# TTK8.net
KiCad netlist of a schematic drawn in Altium Designer
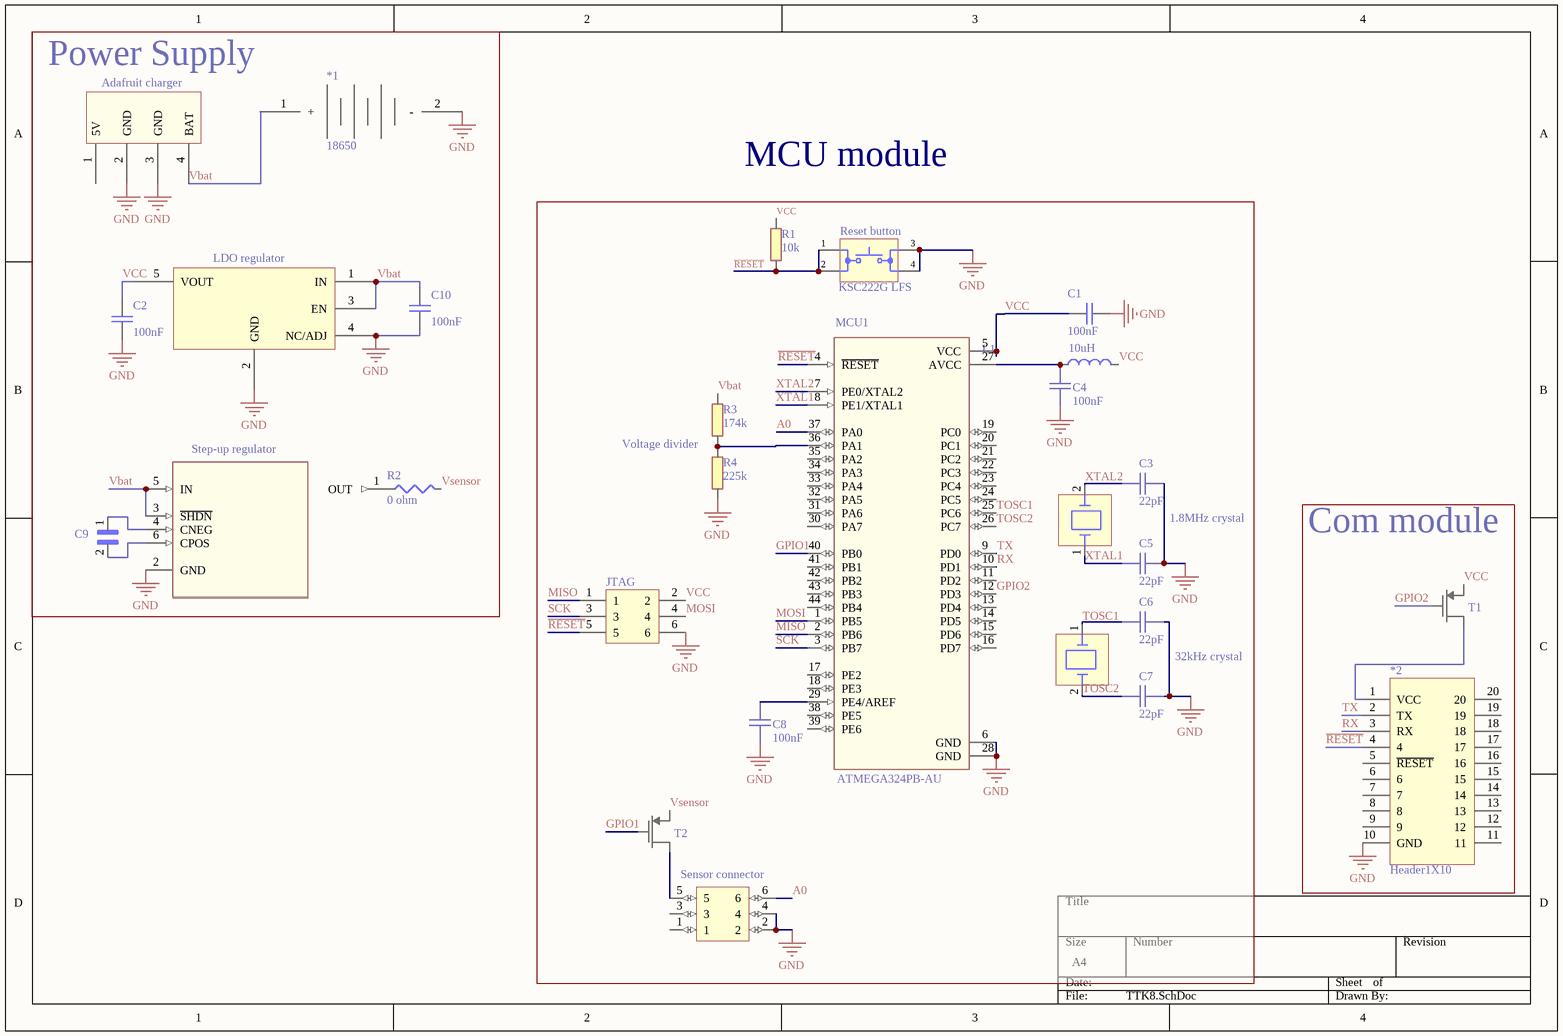
[diagram p0: TTK8.SchDoc]

(export (version "E")
  (design (tool "Eeschema 10.0.6"))
  (components
    (comp (ref "*1") (value "18650") (footprint "18650") (libsource (lib "BatteryHolder") (part "18650")))
    (comp (ref "*2")
      (value "Header1X10")
      (footprint "Header1X10")
      (libsource (lib "Header") (part "Header1X10"))
    )
    (comp (ref "C1")
      (value "100nF")
      (footprint "C0603")
      (description "C0603")
      (fields (field (name "Comment") "02016D104KAT2A"))
      (libsource (lib "Passive components") (part "02016D104KAT2A"))
    )
    (comp (ref "C2")
      (value "100nF")
      (footprint "C0603")
      (description "C0603")
      (fields (field (name "Comment") "02016D104KAT2A"))
      (libsource (lib "Passive components") (part "02016D104KAT2A"))
    )
    (comp (ref "C3")
      (value "22pF")
      (footprint "CAPC0805(2012)100_N")
      (description "50v,")
      (libsource (lib "OVLib_64") (part "CAP"))
    )
    (comp (ref "C4")
      (value "100nF")
      (footprint "CAPC0603(1608)55_N")
      (description "X7R 50V 5%")
      (libsource (lib "OVLib_64") (part "CAP"))
    )
    (comp (ref "C5")
      (value "22pF")
      (footprint "CAPC0805(2012)100_N")
      (description "50v,")
      (libsource (lib "OVLib_64") (part "CAP"))
    )
    (comp (ref "C6")
      (value "22pF")
      (footprint "CAPC0805(2012)100_N")
      (description "50v,")
      (libsource (lib "OVLib_64") (part "CAP"))
    )
    (comp (ref "C7")
      (value "22pF")
      (footprint "CAPC0805(2012)100_N")
      (description "50v,")
      (libsource (lib "OVLib_64") (part "CAP"))
    )
    (comp (ref "C8")
      (value "100nF")
      (footprint "CAPC0603(1608)55_N")
      (description "X7R 50V 5%")
      (libsource (lib "OVLib_64") (part "CAP"))
    )
    (comp (ref "C9")
      (value "C0603C105K8PACTU")
      (footprint "C0603C105K8PACTU")
      (description "C0603")
      (libsource (lib "Passive components") (part "C0603C105K8PACTU"))
    )
    (comp (ref "C10")
      (value "100nF")
      (footprint "C0603")
      (description "C0603")
      (fields (field (name "Comment") "02016D104KAT2A"))
      (libsource (lib "Passive components") (part "02016D104KAT2A"))
    )
    (comp (ref "J1")
      (value "Header 2x3")
      (footprint "Header 2x3 2.54mm")
      (description "Header  2x3 2.54mm male")
      (libsource (lib "Connectors") (part "67996-406HLF"))
    )
    (comp (ref "JTAG")
      (value "123-34-2234_1")
      (footprint "Header 2x3 male")
      (description "Header 2x3 male 2.54mm")
      (libsource (lib "Connectors") (part "123-34-2234_1"))
    )
    (comp (ref "L1")
      (value "10uH")
      (footprint "Inductor 0603")
      (description "Inductor 0603")
      (fields (field (name "Comment") "MLZ1608A2R2WT"))
      (libsource (lib "Passive components") (part "MLZ1608A2R2WT"))
    )
    (comp (ref "MCU1")
      (value "ATMEGA324PB-AU")
      (footprint "*QFP80P1200X1200X120-44N")
      (description "Avr, 32kb Flash, 1kb Ee, 2kb Ram - 20mhz, Tqfp, Ind Temp, Green 5 v/ Tqfp _a_")
      (fields (field (name "MF") "Microchip"))
      (libsource (lib "ATMEGA324PB-AU") (part "ATMEGA324PB-AU"))
    )
    (comp (ref "R1")
      (value "10k")
      (footprint "RESC0603(1608)_N")
      (description "0.1W 1% Thick film resistor")
      (libsource (lib "OVLib_64") (part "Resistor2"))
    )
    (comp (ref "R2")
      (value "0 ohm")
      (footprint "R0402")
      (description "R0402")
      (fields (field (name "Comment") "CRCW04020000Z0ED"))
      (libsource (lib "Passive components") (part "CRCW04020000Z0ED"))
    )
    (comp (ref "R3")
      (value "174k")
      (footprint "RESC0603(1608)_N")
      (description "0.1W 1% Thick film resistor")
      (libsource (lib "OVLib_64") (part "Resistor2"))
    )
    (comp (ref "R4")
      (value "225k")
      (footprint "RESC0603(1608)_N")
      (description "0.1W 1% Thick film resistor")
      (libsource (lib "OVLib_64") (part "Resistor2"))
    )
    (comp (ref "reg1")
      (value "CAT3200TDI-GT3")
      (footprint "CAT3200TDI-GT3")
      (description "Switch-mode step up reg")
      (libsource (lib "Voltage regulators") (part "CAT3200TDI-GT3"))
    )
    (comp (ref "Reset1")
      (value "KSC222G LFS")
      (footprint "KSC222G LFS")
      (description "Button SMD")
      (libsource (lib "Sensors") (part "KSC222G LFS"))
    )
    (comp (ref "T1")
      (value "DMP1045U")
      (footprint "DMP1045U")
      (description "PMOS 5.2A -550mV")
      (libsource (lib "Transistors") (part "DMP1045U"))
    )
    (comp (ref "T2")
      (value "DMP1045U")
      (footprint "DMP1045U")
      (description "PMOS 5.2A -550mV")
      (libsource (lib "Transistors") (part "DMP1045U"))
    )
    (comp (ref "U1") (value "AdaUSBC") (footprint "AdaUSBC") (libsource (lib "Charger") (part "AdaUSBC")))
    (comp (ref "U2")
      (value "NCP718ASN250T1G")
      (footprint "NCP718ASN250T1G")
      (libsource (lib "18432Crystal") (part "NCP718ASN250T1G"))
    )
    (comp (ref "Y1")
      (value "AB-1.8432MHZ-B2")
      (footprint "AB-1.8432MHZ-B2")
      (description "Crystal 1.8432MHz")
      (libsource (lib "18432Crystal") (part "AB-1.8432MHZ-B2"))
    )
    (comp (ref "Y2")
      (value "9HT10-32.768KEZC-T")
      (footprint "9HT10-32.768KEZC-T")
      (description "Crystal 32.768kHz, SMD, 3.2mm x 1.5mm, 9pF, 10 ppm")
      (libsource (lib "Crystal-Molvik") (part "9HT10-32.768KEZC-T"))
    )
  )
  (nets
    (net (code "1") (name "/A0") (class "Default")
      (node (ref "J1") (pin "6") (pinfunction "6_6") (pintype "bidirectional"))
      (node (ref "MCU1") (pin "37") (pinfunction "PA0_37") (pintype "bidirectional"))
    )
    (net (code "2") (name "/GPIO1") (class "Default")
      (node (ref "MCU1") (pin "40") (pinfunction "PB0_40") (pintype "bidirectional"))
      (node (ref "T2") (pin "1") (pinfunction "G_1") (pintype "passive"))
    )
    (net (code "3") (name "/GPIO2") (class "Default")
      (node (ref "MCU1") (pin "12") (pinfunction "PD3_12") (pintype "bidirectional"))
      (node (ref "T1") (pin "1") (pinfunction "G_1") (pintype "passive"))
    )
    (net (code "4") (name "/MISO") (class "Default")
      (node (ref "JTAG") (pin "1") (pinfunction "1_1") (pintype "passive"))
      (node (ref "MCU1") (pin "2") (pinfunction "PB6_2") (pintype "bidirectional"))
    )
    (net (code "5") (name "/MOSI") (class "Default")
      (node (ref "JTAG") (pin "4") (pinfunction "4_4") (pintype "passive"))
      (node (ref "MCU1") (pin "1") (pinfunction "PB5_1") (pintype "bidirectional"))
    )
    (net (code "6") (name "/RX") (class "Default")
      (node (ref "*2") (pin "3") (pinfunction "RX_3") (pintype "passive"))
      (node (ref "MCU1") (pin "10") (pinfunction "PD1_10") (pintype "bidirectional"))
    )
    (net (code "7") (name "/SCK") (class "Default")
      (node (ref "JTAG") (pin "3") (pinfunction "3_3") (pintype "passive"))
      (node (ref "MCU1") (pin "3") (pinfunction "PB7_3") (pintype "bidirectional"))
    )
    (net (code "8") (name "/TOSC1") (class "Default")
      (node (ref "C6") (pin "1") (pinfunction "1_1") (pintype "passive"))
      (node (ref "MCU1") (pin "25") (pinfunction "PC6_25") (pintype "bidirectional"))
      (node (ref "Y2") (pin "1") (pinfunction "2_1") (pintype "passive"))
    )
    (net (code "9") (name "/TOSC2") (class "Default")
      (node (ref "C7") (pin "1") (pinfunction "1_1") (pintype "passive"))
      (node (ref "MCU1") (pin "26") (pinfunction "PC7_26") (pintype "bidirectional"))
      (node (ref "Y2") (pin "2") (pinfunction "2_2") (pintype "passive"))
    )
    (net (code "10") (name "/TX") (class "Default")
      (node (ref "*2") (pin "2") (pinfunction "TX_2") (pintype "passive"))
      (node (ref "MCU1") (pin "9") (pinfunction "PD0_9") (pintype "bidirectional"))
    )
    (net (code "11") (name "/VCC") (class "Default")
      (node (ref "C1") (pin "2") (pinfunction "2_2") (pintype "passive"))
      (node (ref "C2") (pin "2") (pinfunction "2_2") (pintype "passive"))
      (node (ref "JTAG") (pin "2") (pinfunction "2_2") (pintype "passive"))
      (node (ref "L1") (pin "2") (pinfunction "2_2") (pintype "passive"))
      (node (ref "MCU1") (pin "5") (pinfunction "VCC_5") (pintype "power_in"))
      (node (ref "R1") (pin "2") (pinfunction "2_2") (pintype "passive"))
      (node (ref "T1") (pin "2") (pinfunction "S_2") (pintype "passive"))
      (node (ref "U2") (pin "5") (pinfunction "VOUT_5") (pintype "passive"))
    )
    (net (code "12") (name "/Vbat") (class "Default")
      (node (ref "*1") (pin "1") (pinfunction "+_1") (pintype "passive"))
      (node (ref "C10") (pin "2") (pinfunction "2_2") (pintype "passive"))
      (node (ref "R3") (pin "2") (pinfunction "2_2") (pintype "passive"))
      (node (ref "U1") (pin "4") (pinfunction "BAT_4") (pintype "passive"))
      (node (ref "U2") (pin "1") (pinfunction "IN_1") (pintype "passive"))
      (node (ref "U2") (pin "3") (pinfunction "EN_3") (pintype "passive"))
      (node (ref "reg1") (pin "3") (pinfunction "~{SHDN}_3") (pintype "input"))
      (node (ref "reg1") (pin "5") (pinfunction "IN_5") (pintype "input"))
    )
    (net (code "13") (name "/Vsensor") (class "Default")
      (node (ref "R2") (pin "2") (pinfunction "2_2") (pintype "passive"))
      (node (ref "T2") (pin "2") (pinfunction "S_2") (pintype "passive"))
    )
    (net (code "14") (name "/XTAL1") (class "Default")
      (node (ref "C5") (pin "1") (pinfunction "1_1") (pintype "passive"))
      (node (ref "MCU1") (pin "8") (pinfunction "PE1/XTAL1_8") (pintype "input"))
      (node (ref "Y1") (pin "1") (pinfunction "2_1") (pintype "passive"))
    )
    (net (code "15") (name "/XTAL2") (class "Default")
      (node (ref "C3") (pin "1") (pinfunction "1_1") (pintype "passive"))
      (node (ref "MCU1") (pin "7") (pinfunction "PE0/XTAL2_7") (pintype "input"))
      (node (ref "Y1") (pin "2") (pinfunction "2_2") (pintype "passive"))
    )
    (net (code "16") (name "/~{RESET}") (class "Default")
      (node (ref "*2") (pin "4") (pinfunction "4_4") (pintype "passive"))
      (node (ref "JTAG") (pin "5") (pinfunction "5_5") (pintype "passive"))
      (node (ref "MCU1") (pin "4") (pinfunction "~{RESET}_4") (pintype "input"))
      (node (ref "R1") (pin "1") (pinfunction "1_1") (pintype "passive"))
      (node (ref "Reset1") (pin "1") (pinfunction "1_1") (pintype "passive"))
      (node (ref "Reset1") (pin "2") (pinfunction "2_2") (pintype "passive"))
    )
    (net (code "17") (name "GND") (class "Default")
      (node (ref "*1") (pin "2") (pinfunction "-_2") (pintype "passive"))
      (node (ref "*2") (pin "10") (pinfunction "GND_10") (pintype "passive"))
      (node (ref "C1") (pin "1") (pinfunction "1_1") (pintype "passive"))
      (node (ref "C10") (pin "1") (pinfunction "1_1") (pintype "passive"))
      (node (ref "C2") (pin "1") (pinfunction "1_1") (pintype "passive"))
      (node (ref "C3") (pin "2") (pinfunction "2_2") (pintype "passive"))
      (node (ref "C4") (pin "1") (pinfunction "1_1") (pintype "passive"))
      (node (ref "C5") (pin "2") (pinfunction "2_2") (pintype "passive"))
      (node (ref "C6") (pin "2") (pinfunction "2_2") (pintype "passive"))
      (node (ref "C7") (pin "2") (pinfunction "2_2") (pintype "passive"))
      (node (ref "C8") (pin "1") (pinfunction "1_1") (pintype "passive"))
      (node (ref "J1") (pin "2") (pinfunction "2_2") (pintype "bidirectional"))
      (node (ref "J1") (pin "4") (pinfunction "4_4") (pintype "bidirectional"))
      (node (ref "JTAG") (pin "6") (pinfunction "6_6") (pintype "passive"))
      (node (ref "MCU1") (pin "28") (pinfunction "GND_28") (pintype "power_in"))
      (node (ref "MCU1") (pin "6") (pinfunction "GND_6") (pintype "power_in"))
      (node (ref "R4") (pin "1") (pinfunction "1_1") (pintype "passive"))
      (node (ref "Reset1") (pin "3") (pinfunction "3_3") (pintype "passive"))
      (node (ref "Reset1") (pin "4") (pinfunction "4_4") (pintype "passive"))
      (node (ref "U1") (pin "2") (pinfunction "GND_2") (pintype "passive"))
      (node (ref "U1") (pin "3") (pinfunction "GND_3") (pintype "passive"))
      (node (ref "U2") (pin "2") (pinfunction "GND_2") (pintype "passive"))
      (node (ref "U2") (pin "4") (pinfunction "NC/ADJ_4") (pintype "passive"))
      (node (ref "reg1") (pin "2") (pinfunction "GND_2") (pintype "passive"))
    )
    (net (code "18") (name "Net-(*2-VCC)") (class "Default")
      (node (ref "*2") (pin "1") (pinfunction "VCC_1") (pintype "passive"))
      (node (ref "T1") (pin "3") (pinfunction "D_3") (pintype "passive"))
    )
    (net (code "19") (name "Net-(MCU1-AVCC)") (class "Default")
      (node (ref "C4") (pin "2") (pinfunction "2_2") (pintype "passive"))
      (node (ref "L1") (pin "1") (pinfunction "1_1") (pintype "passive"))
      (node (ref "MCU1") (pin "27") (pinfunction "AVCC_27") (pintype "power_in"))
    )
    (net (code "20") (name "Net-(MCU1-PA1)") (class "Default")
      (node (ref "MCU1") (pin "36") (pinfunction "PA1_36") (pintype "bidirectional"))
      (node (ref "R3") (pin "1") (pinfunction "1_1") (pintype "passive"))
      (node (ref "R4") (pin "2") (pinfunction "2_2") (pintype "passive"))
    )
    (net (code "21") (name "Net-(MCU1-PE4{slash}AREF)") (class "Default")
      (node (ref "C8") (pin "2") (pinfunction "2_2") (pintype "passive"))
      (node (ref "MCU1") (pin "29") (pinfunction "PE4/AREF_29") (pintype "input"))
    )
    (net (code "22") (name "Net-(T2-D)") (class "Default")
      (node (ref "J1") (pin "5") (pinfunction "5_5") (pintype "bidirectional"))
      (node (ref "T2") (pin "3") (pinfunction "D_3") (pintype "passive"))
    )
    (net (code "23") (name "Net-(reg1-CNEG)") (class "Default")
      (node (ref "C9") (pin "1") (pinfunction "1_1") (pintype "passive"))
      (node (ref "reg1") (pin "4") (pinfunction "CNEG_4") (pintype "input"))
    )
    (net (code "24") (name "Net-(reg1-CPOS)") (class "Default")
      (node (ref "C9") (pin "2") (pinfunction "2_2") (pintype "passive"))
      (node (ref "reg1") (pin "6") (pinfunction "CPOS_6") (pintype "input"))
    )
    (net (code "25") (name "Net-(reg1-OUT)") (class "Default")
      (node (ref "R2") (pin "1") (pinfunction "1_1") (pintype "passive"))
      (node (ref "reg1") (pin "1") (pinfunction "OUT_1") (pintype "output"))
    )
    (net (code "26") (name "unconnected-(*2-Pad6)") (class "Default")
      (node (ref "*2") (pin "6") (pinfunction "6_6") (pintype "passive"))
    )
    (net (code "27") (name "unconnected-(*2-Pad7)") (class "Default")
      (node (ref "*2") (pin "7") (pinfunction "7_7") (pintype "passive"))
    )
    (net (code "28") (name "unconnected-(*2-Pad8)") (class "Default")
      (node (ref "*2") (pin "8") (pinfunction "8_8") (pintype "passive"))
    )
    (net (code "29") (name "unconnected-(*2-Pad9)") (class "Default")
      (node (ref "*2") (pin "9") (pinfunction "9_9") (pintype "passive"))
    )
    (net (code "30") (name "unconnected-(*2-Pad11)") (class "Default")
      (node (ref "*2") (pin "11") (pinfunction "11_11") (pintype "passive"))
    )
    (net (code "31") (name "unconnected-(*2-Pad12)") (class "Default")
      (node (ref "*2") (pin "12") (pinfunction "12_12") (pintype "passive"))
    )
    (net (code "32") (name "unconnected-(*2-Pad13)") (class "Default")
      (node (ref "*2") (pin "13") (pinfunction "13_13") (pintype "passive"))
    )
    (net (code "33") (name "unconnected-(*2-Pad14)") (class "Default")
      (node (ref "*2") (pin "14") (pinfunction "14_14") (pintype "passive"))
    )
    (net (code "34") (name "unconnected-(*2-Pad15)") (class "Default")
      (node (ref "*2") (pin "15") (pinfunction "15_15") (pintype "passive"))
    )
    (net (code "35") (name "unconnected-(*2-Pad16)") (class "Default")
      (node (ref "*2") (pin "16") (pinfunction "16_16") (pintype "passive"))
    )
    (net (code "36") (name "unconnected-(*2-Pad17)") (class "Default")
      (node (ref "*2") (pin "17") (pinfunction "17_17") (pintype "passive"))
    )
    (net (code "37") (name "unconnected-(*2-Pad18)") (class "Default")
      (node (ref "*2") (pin "18") (pinfunction "18_18") (pintype "passive"))
    )
    (net (code "38") (name "unconnected-(*2-Pad19)") (class "Default")
      (node (ref "*2") (pin "19") (pinfunction "19_19") (pintype "passive"))
    )
    (net (code "39") (name "unconnected-(*2-Pad20)") (class "Default")
      (node (ref "*2") (pin "20") (pinfunction "20_20") (pintype "passive"))
    )
    (net (code "40") (name "unconnected-(*2-~{RESET}-Pad5)") (class "Default")
      (node (ref "*2") (pin "5") (pinfunction "~{RESET}_5") (pintype "passive"))
    )
    (net (code "41") (name "unconnected-(J1-Pad1)") (class "Default")
      (node (ref "J1") (pin "1") (pinfunction "1_1") (pintype "bidirectional"))
    )
    (net (code "42") (name "unconnected-(J1-Pad3)") (class "Default")
      (node (ref "J1") (pin "3") (pinfunction "3_3") (pintype "bidirectional"))
    )
    (net (code "43") (name "unconnected-(MCU1-PA2-Pad35)") (class "Default")
      (node (ref "MCU1") (pin "35") (pinfunction "PA2_35") (pintype "bidirectional"))
    )
    (net (code "44") (name "unconnected-(MCU1-PA3-Pad34)") (class "Default")
      (node (ref "MCU1") (pin "34") (pinfunction "PA3_34") (pintype "bidirectional"))
    )
    (net (code "45") (name "unconnected-(MCU1-PA4-Pad33)") (class "Default")
      (node (ref "MCU1") (pin "33") (pinfunction "PA4_33") (pintype "bidirectional"))
    )
    (net (code "46") (name "unconnected-(MCU1-PA5-Pad32)") (class "Default")
      (node (ref "MCU1") (pin "32") (pinfunction "PA5_32") (pintype "bidirectional"))
    )
    (net (code "47") (name "unconnected-(MCU1-PA6-Pad31)") (class "Default")
      (node (ref "MCU1") (pin "31") (pinfunction "PA6_31") (pintype "bidirectional"))
    )
    (net (code "48") (name "unconnected-(MCU1-PA7-Pad30)") (class "Default")
      (node (ref "MCU1") (pin "30") (pinfunction "PA7_30") (pintype "bidirectional"))
    )
    (net (code "49") (name "unconnected-(MCU1-PB1-Pad41)") (class "Default")
      (node (ref "MCU1") (pin "41") (pinfunction "PB1_41") (pintype "bidirectional"))
    )
    (net (code "50") (name "unconnected-(MCU1-PB2-Pad42)") (class "Default")
      (node (ref "MCU1") (pin "42") (pinfunction "PB2_42") (pintype "bidirectional"))
    )
    (net (code "51") (name "unconnected-(MCU1-PB3-Pad43)") (class "Default")
      (node (ref "MCU1") (pin "43") (pinfunction "PB3_43") (pintype "bidirectional"))
    )
    (net (code "52") (name "unconnected-(MCU1-PB4-Pad44)") (class "Default")
      (node (ref "MCU1") (pin "44") (pinfunction "PB4_44") (pintype "bidirectional"))
    )
    (net (code "53") (name "unconnected-(MCU1-PC0-Pad19)") (class "Default")
      (node (ref "MCU1") (pin "19") (pinfunction "PC0_19") (pintype "bidirectional"))
    )
    (net (code "54") (name "unconnected-(MCU1-PC1-Pad20)") (class "Default")
      (node (ref "MCU1") (pin "20") (pinfunction "PC1_20") (pintype "bidirectional"))
    )
    (net (code "55") (name "unconnected-(MCU1-PC2-Pad21)") (class "Default")
      (node (ref "MCU1") (pin "21") (pinfunction "PC2_21") (pintype "bidirectional"))
    )
    (net (code "56") (name "unconnected-(MCU1-PC3-Pad22)") (class "Default")
      (node (ref "MCU1") (pin "22") (pinfunction "PC3_22") (pintype "bidirectional"))
    )
    (net (code "57") (name "unconnected-(MCU1-PC4-Pad23)") (class "Default")
      (node (ref "MCU1") (pin "23") (pinfunction "PC4_23") (pintype "bidirectional"))
    )
    (net (code "58") (name "unconnected-(MCU1-PC5-Pad24)") (class "Default")
      (node (ref "MCU1") (pin "24") (pinfunction "PC5_24") (pintype "bidirectional"))
    )
    (net (code "59") (name "unconnected-(MCU1-PD2-Pad11)") (class "Default")
      (node (ref "MCU1") (pin "11") (pinfunction "PD2_11") (pintype "bidirectional"))
    )
    (net (code "60") (name "unconnected-(MCU1-PD4-Pad13)") (class "Default")
      (node (ref "MCU1") (pin "13") (pinfunction "PD4_13") (pintype "bidirectional"))
    )
    (net (code "61") (name "unconnected-(MCU1-PD5-Pad14)") (class "Default")
      (node (ref "MCU1") (pin "14") (pinfunction "PD5_14") (pintype "bidirectional"))
    )
    (net (code "62") (name "unconnected-(MCU1-PD6-Pad15)") (class "Default")
      (node (ref "MCU1") (pin "15") (pinfunction "PD6_15") (pintype "bidirectional"))
    )
    (net (code "63") (name "unconnected-(MCU1-PD7-Pad16)") (class "Default")
      (node (ref "MCU1") (pin "16") (pinfunction "PD7_16") (pintype "bidirectional"))
    )
    (net (code "64") (name "unconnected-(MCU1-PE2-Pad17)") (class "Default")
      (node (ref "MCU1") (pin "17") (pinfunction "PE2_17") (pintype "bidirectional"))
    )
    (net (code "65") (name "unconnected-(MCU1-PE3-Pad18)") (class "Default")
      (node (ref "MCU1") (pin "18") (pinfunction "PE3_18") (pintype "bidirectional"))
    )
    (net (code "66") (name "unconnected-(MCU1-PE5-Pad38)") (class "Default")
      (node (ref "MCU1") (pin "38") (pinfunction "PE5_38") (pintype "bidirectional"))
    )
    (net (code "67") (name "unconnected-(MCU1-PE6-Pad39)") (class "Default")
      (node (ref "MCU1") (pin "39") (pinfunction "PE6_39") (pintype "bidirectional"))
    )
    (net (code "68") (name "unconnected-(U1-5V-Pad1)") (class "Default")
      (node (ref "U1") (pin "1") (pinfunction "5V_1") (pintype "passive"))
    )
  )
)
